# SQR_FG_Output.net
KiCad netlist of a schematic drawn in EAGLE
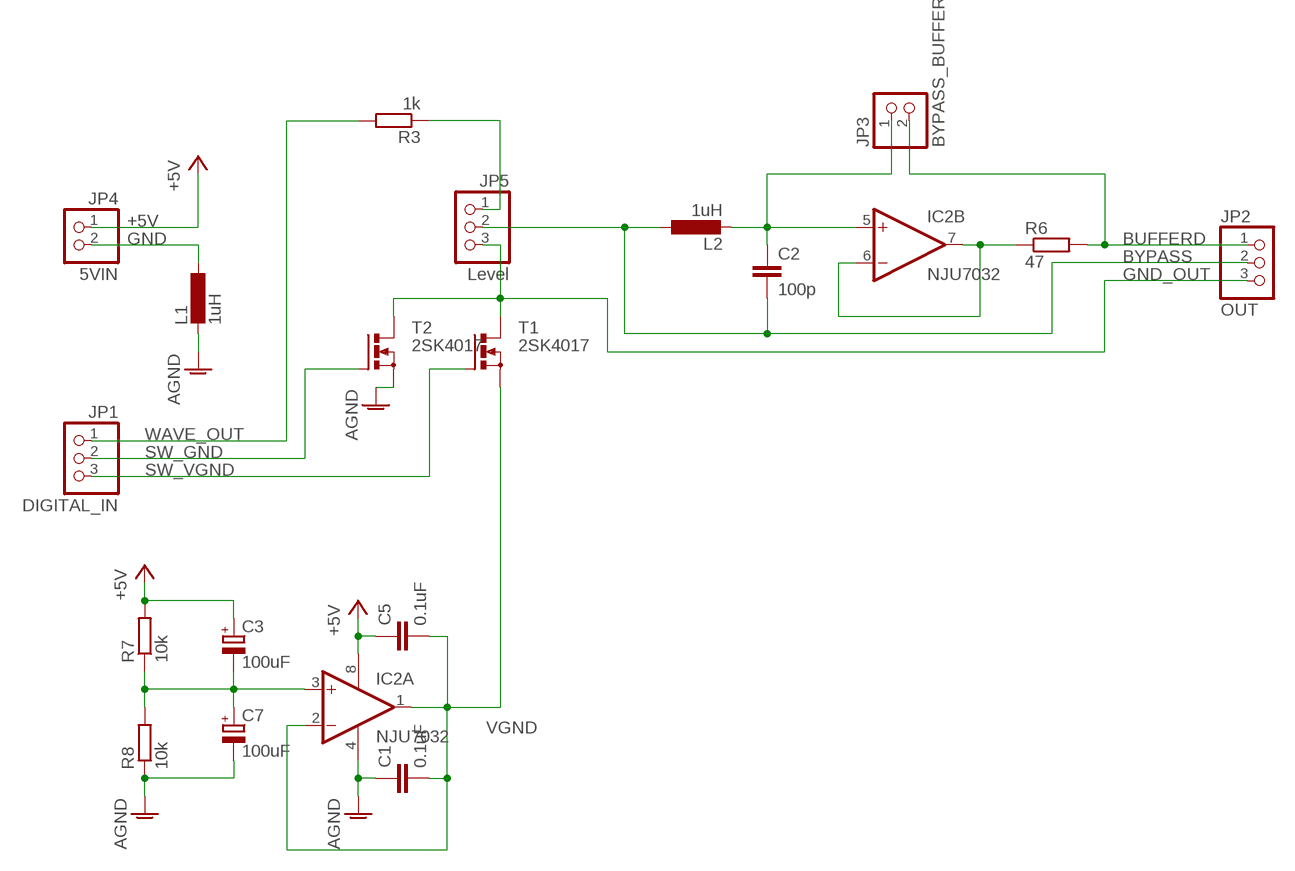
[diagram p0: schematic, sheet 1]

(export (version "E")
  (design (tool "Eeschema 10.0.6"))
  (components
    (comp (ref "C1")
      (value "0.1uF")
      (footprint "eagle-import:C025-024X044")
      (libsource (lib "eagle-import") (part "C-EU025-024X044"))
    )
    (comp (ref "C2")
      (value "100p")
      (footprint "eagle-import:C075-032X103")
      (libsource (lib "eagle-import") (part "C-EU075-032X103"))
    )
    (comp (ref "C3")
      (value "100uF")
      (footprint "eagle-import:E2,5-5")
      (libsource (lib "eagle-import") (part "CPOL-EUE2.5-5"))
    )
    (comp (ref "C5")
      (value "0.1uF")
      (footprint "eagle-import:C025-024X044")
      (libsource (lib "eagle-import") (part "C-EU025-024X044"))
    )
    (comp (ref "C7")
      (value "100uF")
      (footprint "eagle-import:E2,5-5")
      (libsource (lib "eagle-import") (part "CPOL-EUE2.5-5"))
    )
    (comp (ref "IC2")
      (value "NJU7032")
      (footprint "eagle-import:DIL08")
      (libsource (lib "eagle-import") (part "LM358N"))
    )
    (comp (ref "JP1")
      (value "DIGITAL_IN")
      (footprint "eagle-import:1X03")
      (libsource (lib "eagle-import") (part "PINHD-1X3"))
    )
    (comp (ref "JP2")
      (value "OUT")
      (footprint "eagle-import:1X03")
      (libsource (lib "eagle-import") (part "PINHD-1X3"))
    )
    (comp (ref "JP3")
      (value "BYPASS_BUFFER")
      (footprint "eagle-import:1X02")
      (libsource (lib "eagle-import") (part "PINHD-1X2"))
    )
    (comp (ref "JP4")
      (value "5VIN")
      (footprint "eagle-import:1X02")
      (libsource (lib "eagle-import") (part "PINHD-1X2"))
    )
    (comp (ref "JP5")
      (value "Level")
      (footprint "eagle-import:1X03")
      (libsource (lib "eagle-import") (part "PINHD-1X3"))
    )
    (comp (ref "L1")
      (value "1uH")
      (footprint "eagle-import:0204_7")
      (libsource (lib "eagle-import") (part "L-EU0204/7"))
    )
    (comp (ref "L2")
      (value "1uH")
      (footprint "eagle-import:0204_7")
      (libsource (lib "eagle-import") (part "L-EU0204/7"))
    )
    (comp (ref "R3")
      (value "1k")
      (footprint "eagle-import:0207_7")
      (libsource (lib "eagle-import") (part "R-EU_0207/7"))
    )
    (comp (ref "R6")
      (value "47")
      (footprint "eagle-import:0207_7")
      (libsource (lib "eagle-import") (part "R-EU_0207/7"))
    )
    (comp (ref "R7")
      (value "10k")
      (footprint "eagle-import:0207_7")
      (libsource (lib "eagle-import") (part "R-EU_0207/7"))
    )
    (comp (ref "R8")
      (value "10k")
      (footprint "eagle-import:0207_7")
      (libsource (lib "eagle-import") (part "R-EU_0207/7"))
    )
    (comp (ref "T1")
      (value "2SK4017")
      (footprint "eagle-import:TO220BV")
      (libsource (lib "eagle-import") (part "BUZ11BV"))
    )
    (comp (ref "T2")
      (value "2SK4017")
      (footprint "eagle-import:TO220BV")
      (libsource (lib "eagle-import") (part "BUZ11BV"))
    )
  )
  (nets
    (net (code "1") (name "+5V") (class "Default")
      (node (ref "C3") (pin "+") (pinfunction "+_+") (pintype "passive"))
      (node (ref "C5") (pin "1") (pinfunction "1_1") (pintype "passive"))
      (node (ref "IC2") (pin "8") (pinfunction "V+_8") (pintype "power_in"))
      (node (ref "JP4") (pin "1") (pinfunction "1_1") (pintype "passive"))
      (node (ref "R7") (pin "2") (pinfunction "2_2") (pintype "passive"))
    )
    (net (code "2") (name "/BUFFERD") (class "Default")
      (node (ref "JP2") (pin "1") (pinfunction "1_1") (pintype "passive"))
      (node (ref "JP3") (pin "2") (pinfunction "2_2") (pintype "passive"))
      (node (ref "R6") (pin "2") (pinfunction "2_2") (pintype "passive"))
    )
    (net (code "3") (name "/BYPASS") (class "Default")
      (node (ref "C2") (pin "2") (pinfunction "2_2") (pintype "passive"))
      (node (ref "JP2") (pin "2") (pinfunction "2_2") (pintype "passive"))
      (node (ref "JP5") (pin "2") (pinfunction "2_2") (pintype "passive"))
      (node (ref "L2") (pin "1") (pinfunction "1_1") (pintype "passive"))
    )
    (net (code "4") (name "/GND") (class "Default")
      (node (ref "JP4") (pin "2") (pinfunction "2_2") (pintype "passive"))
      (node (ref "L1") (pin "1") (pinfunction "1_1") (pintype "passive"))
    )
    (net (code "5") (name "/GND_OUT") (class "Default")
      (node (ref "JP2") (pin "3") (pinfunction "3_3") (pintype "passive"))
      (node (ref "JP5") (pin "3") (pinfunction "3_3") (pintype "passive"))
      (node (ref "T1") (pin "D") (pinfunction "D_D") (pintype "passive"))
      (node (ref "T2") (pin "D") (pinfunction "D_D") (pintype "passive"))
    )
    (net (code "6") (name "/SW_GND") (class "Default")
      (node (ref "JP1") (pin "2") (pinfunction "2_2") (pintype "passive"))
      (node (ref "T2") (pin "G") (pinfunction "G_G") (pintype "passive"))
    )
    (net (code "7") (name "/SW_VGND") (class "Default")
      (node (ref "JP1") (pin "3") (pinfunction "3_3") (pintype "passive"))
      (node (ref "T1") (pin "G") (pinfunction "G_G") (pintype "passive"))
    )
    (net (code "8") (name "/VGND") (class "Default")
      (node (ref "C1") (pin "2") (pinfunction "2_2") (pintype "passive"))
      (node (ref "C5") (pin "2") (pinfunction "2_2") (pintype "passive"))
      (node (ref "IC2") (pin "1") (pinfunction "OUT_1") (pintype "output"))
      (node (ref "IC2") (pin "2") (pinfunction "-IN_2") (pintype "input"))
      (node (ref "T1") (pin "S") (pinfunction "S_S") (pintype "passive"))
    )
    (net (code "9") (name "/WAVE_OUT") (class "Default")
      (node (ref "JP1") (pin "1") (pinfunction "1_1") (pintype "passive"))
      (node (ref "R3") (pin "2") (pinfunction "2_2") (pintype "passive"))
    )
    (net (code "10") (name "AGND") (class "Default")
      (node (ref "C1") (pin "1") (pinfunction "1_1") (pintype "passive"))
      (node (ref "C7") (pin "-") (pinfunction "-_-") (pintype "passive"))
      (node (ref "IC2") (pin "4") (pinfunction "V-_4") (pintype "power_in"))
      (node (ref "L1") (pin "2") (pinfunction "2_2") (pintype "passive"))
      (node (ref "R8") (pin "1") (pinfunction "1_1") (pintype "passive"))
      (node (ref "T2") (pin "S") (pinfunction "S_S") (pintype "passive"))
    )
    (net (code "11") (name "Net-(IC2A-+IN)") (class "Default")
      (node (ref "C3") (pin "-") (pinfunction "-_-") (pintype "passive"))
      (node (ref "C7") (pin "+") (pinfunction "+_+") (pintype "passive"))
      (node (ref "IC2") (pin "3") (pinfunction "+IN_3") (pintype "input"))
      (node (ref "R7") (pin "1") (pinfunction "1_1") (pintype "passive"))
      (node (ref "R8") (pin "2") (pinfunction "2_2") (pintype "passive"))
    )
    (net (code "12") (name "Net-(IC2B-+IN)") (class "Default")
      (node (ref "C2") (pin "1") (pinfunction "1_1") (pintype "passive"))
      (node (ref "IC2") (pin "5") (pinfunction "+IN_5") (pintype "input"))
      (node (ref "JP3") (pin "1") (pinfunction "1_1") (pintype "passive"))
      (node (ref "L2") (pin "2") (pinfunction "2_2") (pintype "passive"))
    )
    (net (code "13") (name "Net-(IC2B--IN)") (class "Default")
      (node (ref "IC2") (pin "6") (pinfunction "-IN_6") (pintype "input"))
      (node (ref "IC2") (pin "7") (pinfunction "OUT_7") (pintype "output"))
      (node (ref "R6") (pin "1") (pinfunction "1_1") (pintype "passive"))
    )
    (net (code "14") (name "Net-(JP5-Pad1)") (class "Default")
      (node (ref "JP5") (pin "1") (pinfunction "1_1") (pintype "passive"))
      (node (ref "R3") (pin "1") (pinfunction "1_1") (pintype "passive"))
    )
  )
)
